# slang-lsm6dsl-prostrednik.net
KiCad netlist of a schematic drawn in EAGLE
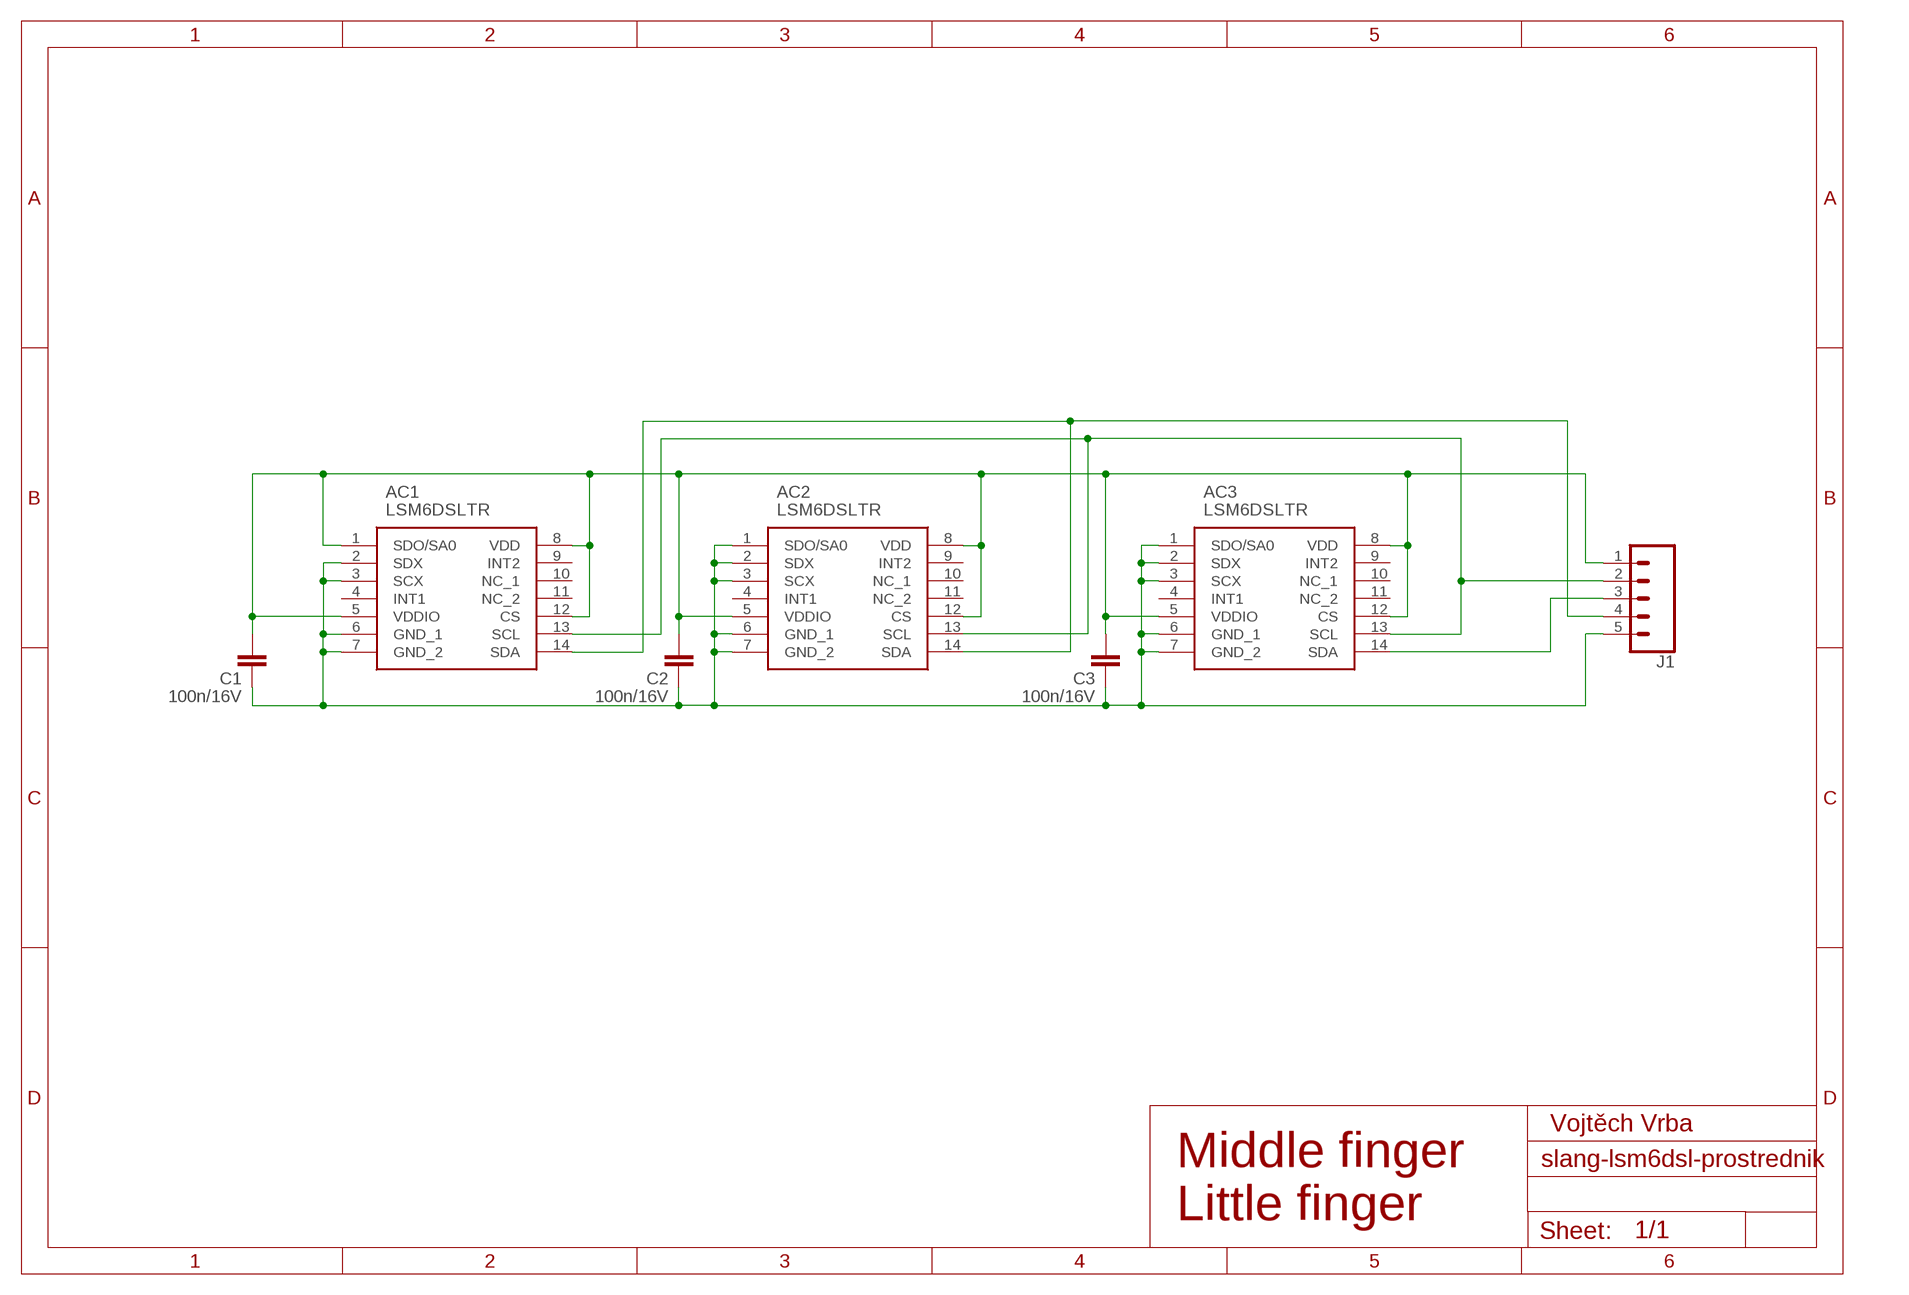
[diagram p0: schematic, sheet 1]

(export (version "E")
  (design (tool "Eeschema 10.0.6"))
  (components
    (comp (ref "AC1")
      (value "LSM6DSLTR")
      (footprint "eagle-import:LGA-14(2.5X3X0.86)")
      (fields (field (name "RS_PART_NUMBER") "1639811P"))
      (libsource (lib "eagle-import") (part "LSM6DSLTR"))
    )
    (comp (ref "AC2")
      (value "LSM6DSLTR")
      (footprint "eagle-import:LGA-14(2.5X3X0.86)")
      (fields (field (name "RS_PART_NUMBER") "1639811P"))
      (libsource (lib "eagle-import") (part "LSM6DSLTR"))
    )
    (comp (ref "AC3")
      (value "LSM6DSLTR")
      (footprint "eagle-import:LGA-14(2.5X3X0.86)")
      (fields (field (name "RS_PART_NUMBER") "1639811P"))
      (libsource (lib "eagle-import") (part "LSM6DSLTR"))
    )
    (comp (ref "C1")
      (value "100n/16V")
      (footprint "eagle-import:C0603")
      (libsource (lib "eagle-import") (part "C-EUC0603"))
    )
    (comp (ref "C2")
      (value "100n/16V")
      (footprint "eagle-import:C0603")
      (libsource (lib "eagle-import") (part "C-EUC0603"))
    )
    (comp (ref "C3")
      (value "100n/16V")
      (footprint "eagle-import:C0603")
      (libsource (lib "eagle-import") (part "C-EUC0603"))
    )
    (comp (ref "J1")
      (value "CONN_051.27MM")
      (footprint "eagle-import:1X05_1.27MM")
      (libsource (lib "eagle-import") (part "CONN_051.27MM"))
    )
  )
  (nets
    (net (code "1") (name "Net-(AC1-CS)") (class "Default")
      (node (ref "AC1") (pin "1") (pinfunction "SDO/SA0_1") (pintype "bidirectional"))
      (node (ref "AC1") (pin "12") (pinfunction "CS_12") (pintype "bidirectional"))
      (node (ref "AC1") (pin "5") (pinfunction "VDDIO_5") (pintype "bidirectional"))
      (node (ref "AC1") (pin "8") (pinfunction "VDD_8") (pintype "bidirectional"))
      (node (ref "AC2") (pin "12") (pinfunction "CS_12") (pintype "bidirectional"))
      (node (ref "AC2") (pin "5") (pinfunction "VDDIO_5") (pintype "bidirectional"))
      (node (ref "AC2") (pin "8") (pinfunction "VDD_8") (pintype "bidirectional"))
      (node (ref "AC3") (pin "12") (pinfunction "CS_12") (pintype "bidirectional"))
      (node (ref "AC3") (pin "5") (pinfunction "VDDIO_5") (pintype "bidirectional"))
      (node (ref "AC3") (pin "8") (pinfunction "VDD_8") (pintype "bidirectional"))
      (node (ref "C1") (pin "2") (pinfunction "2_2") (pintype "passive"))
      (node (ref "C2") (pin "2") (pinfunction "2_2") (pintype "passive"))
      (node (ref "C3") (pin "2") (pinfunction "2_2") (pintype "passive"))
      (node (ref "J1") (pin "1") (pinfunction "1_1") (pintype "passive"))
    )
    (net (code "2") (name "Net-(AC1-GND_1)") (class "Default")
      (node (ref "AC1") (pin "2") (pinfunction "SDX_2") (pintype "bidirectional"))
      (node (ref "AC1") (pin "3") (pinfunction "SCX_3") (pintype "bidirectional"))
      (node (ref "AC1") (pin "6") (pinfunction "GND_1_6") (pintype "bidirectional"))
      (node (ref "AC1") (pin "7") (pinfunction "GND_2_7") (pintype "bidirectional"))
      (node (ref "AC2") (pin "1") (pinfunction "SDO/SA0_1") (pintype "bidirectional"))
      (node (ref "AC2") (pin "2") (pinfunction "SDX_2") (pintype "bidirectional"))
      (node (ref "AC2") (pin "3") (pinfunction "SCX_3") (pintype "bidirectional"))
      (node (ref "AC2") (pin "6") (pinfunction "GND_1_6") (pintype "bidirectional"))
      (node (ref "AC2") (pin "7") (pinfunction "GND_2_7") (pintype "bidirectional"))
      (node (ref "AC3") (pin "1") (pinfunction "SDO/SA0_1") (pintype "bidirectional"))
      (node (ref "AC3") (pin "2") (pinfunction "SDX_2") (pintype "bidirectional"))
      (node (ref "AC3") (pin "3") (pinfunction "SCX_3") (pintype "bidirectional"))
      (node (ref "AC3") (pin "6") (pinfunction "GND_1_6") (pintype "bidirectional"))
      (node (ref "AC3") (pin "7") (pinfunction "GND_2_7") (pintype "bidirectional"))
      (node (ref "C1") (pin "1") (pinfunction "1_1") (pintype "passive"))
      (node (ref "C2") (pin "1") (pinfunction "1_1") (pintype "passive"))
      (node (ref "C3") (pin "1") (pinfunction "1_1") (pintype "passive"))
      (node (ref "J1") (pin "5") (pinfunction "5_5") (pintype "passive"))
    )
    (net (code "3") (name "Net-(AC1-SCL)") (class "Default")
      (node (ref "AC1") (pin "13") (pinfunction "SCL_13") (pintype "bidirectional"))
      (node (ref "AC2") (pin "13") (pinfunction "SCL_13") (pintype "bidirectional"))
      (node (ref "AC3") (pin "13") (pinfunction "SCL_13") (pintype "bidirectional"))
      (node (ref "J1") (pin "2") (pinfunction "2_2") (pintype "passive"))
    )
    (net (code "4") (name "Net-(AC1-SDA)") (class "Default")
      (node (ref "AC1") (pin "14") (pinfunction "SDA_14") (pintype "bidirectional"))
      (node (ref "AC2") (pin "14") (pinfunction "SDA_14") (pintype "bidirectional"))
      (node (ref "J1") (pin "4") (pinfunction "4_4") (pintype "passive"))
    )
    (net (code "5") (name "Net-(AC3-SDA)") (class "Default")
      (node (ref "AC3") (pin "14") (pinfunction "SDA_14") (pintype "bidirectional"))
      (node (ref "J1") (pin "3") (pinfunction "3_3") (pintype "passive"))
    )
    (net (code "6") (name "unconnected-(AC1-INT1-Pad4)") (class "Default")
      (node (ref "AC1") (pin "4") (pinfunction "INT1_4") (pintype "bidirectional"))
    )
    (net (code "7") (name "unconnected-(AC1-INT2-Pad9)") (class "Default")
      (node (ref "AC1") (pin "9") (pinfunction "INT2_9") (pintype "bidirectional"))
    )
    (net (code "8") (name "unconnected-(AC1-NC_1-Pad10)") (class "Default")
      (node (ref "AC1") (pin "10") (pinfunction "NC_1_10") (pintype "bidirectional"))
    )
    (net (code "9") (name "unconnected-(AC1-NC_2-Pad11)") (class "Default")
      (node (ref "AC1") (pin "11") (pinfunction "NC_2_11") (pintype "bidirectional"))
    )
    (net (code "10") (name "unconnected-(AC2-INT1-Pad4)") (class "Default")
      (node (ref "AC2") (pin "4") (pinfunction "INT1_4") (pintype "bidirectional"))
    )
    (net (code "11") (name "unconnected-(AC2-INT2-Pad9)") (class "Default")
      (node (ref "AC2") (pin "9") (pinfunction "INT2_9") (pintype "bidirectional"))
    )
    (net (code "12") (name "unconnected-(AC2-NC_1-Pad10)") (class "Default")
      (node (ref "AC2") (pin "10") (pinfunction "NC_1_10") (pintype "bidirectional"))
    )
    (net (code "13") (name "unconnected-(AC2-NC_2-Pad11)") (class "Default")
      (node (ref "AC2") (pin "11") (pinfunction "NC_2_11") (pintype "bidirectional"))
    )
    (net (code "14") (name "unconnected-(AC3-INT1-Pad4)") (class "Default")
      (node (ref "AC3") (pin "4") (pinfunction "INT1_4") (pintype "bidirectional"))
    )
    (net (code "15") (name "unconnected-(AC3-INT2-Pad9)") (class "Default")
      (node (ref "AC3") (pin "9") (pinfunction "INT2_9") (pintype "bidirectional"))
    )
    (net (code "16") (name "unconnected-(AC3-NC_1-Pad10)") (class "Default")
      (node (ref "AC3") (pin "10") (pinfunction "NC_1_10") (pintype "bidirectional"))
    )
    (net (code "17") (name "unconnected-(AC3-NC_2-Pad11)") (class "Default")
      (node (ref "AC3") (pin "11") (pinfunction "NC_2_11") (pintype "bidirectional"))
    )
  )
)
